# CHEM_CONTROL_BOX.net
KiCad netlist of a schematic drawn in Altium Designer
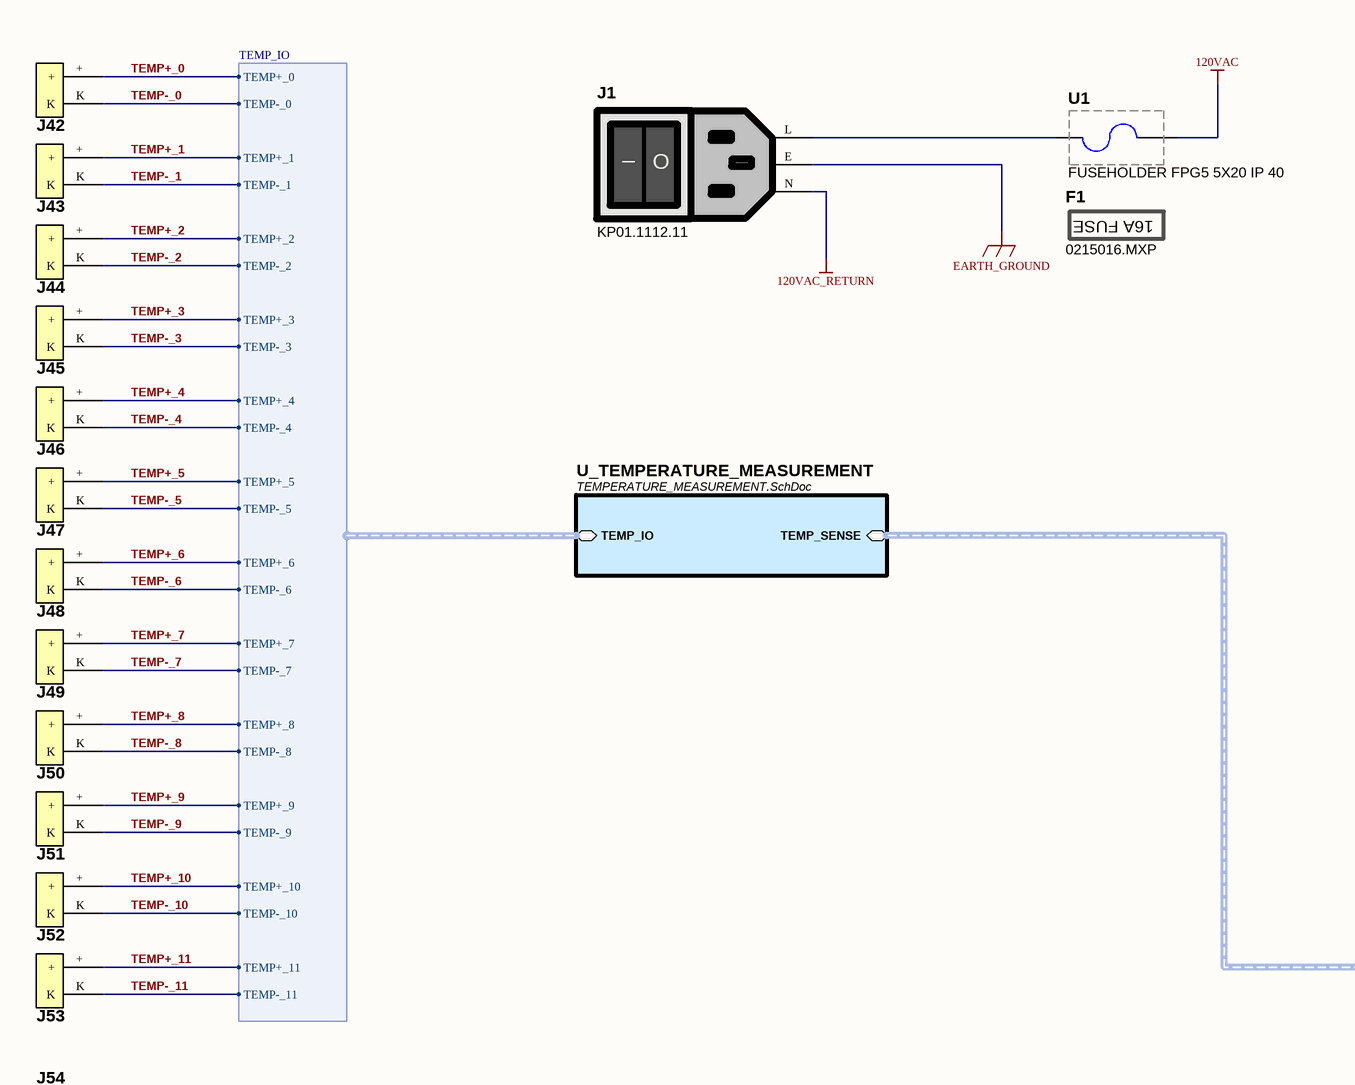
[diagram p0: CHEM_CONTROL_BOX.SchDoc, top left]
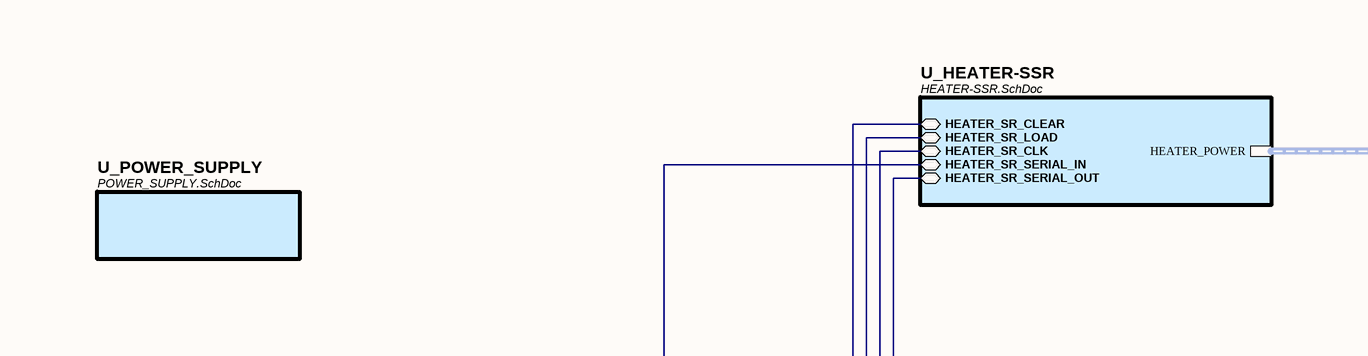
[diagram p1: CHEM_CONTROL_BOX.SchDoc, top middle]
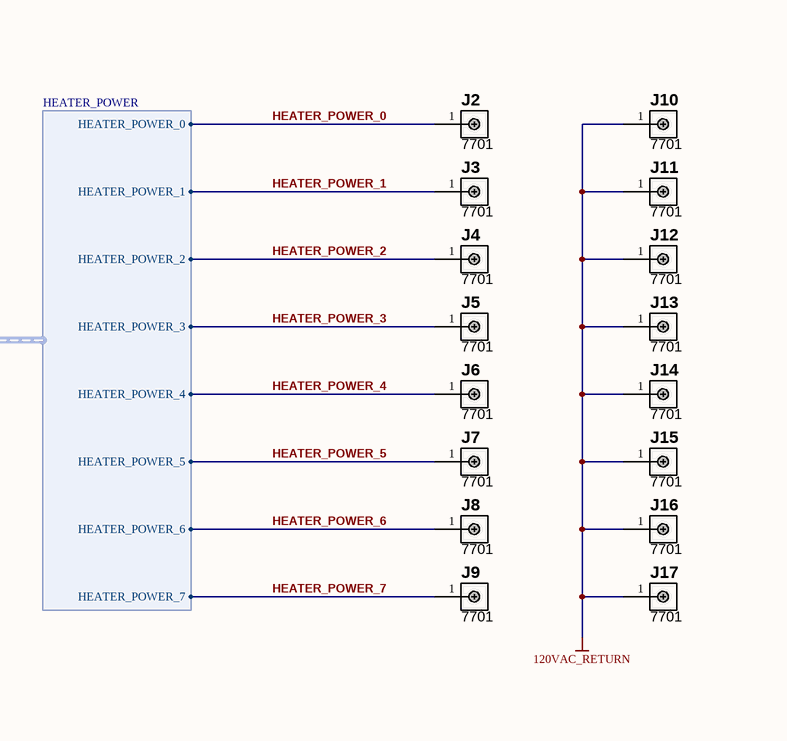
[diagram p2: CHEM_CONTROL_BOX.SchDoc, top right]
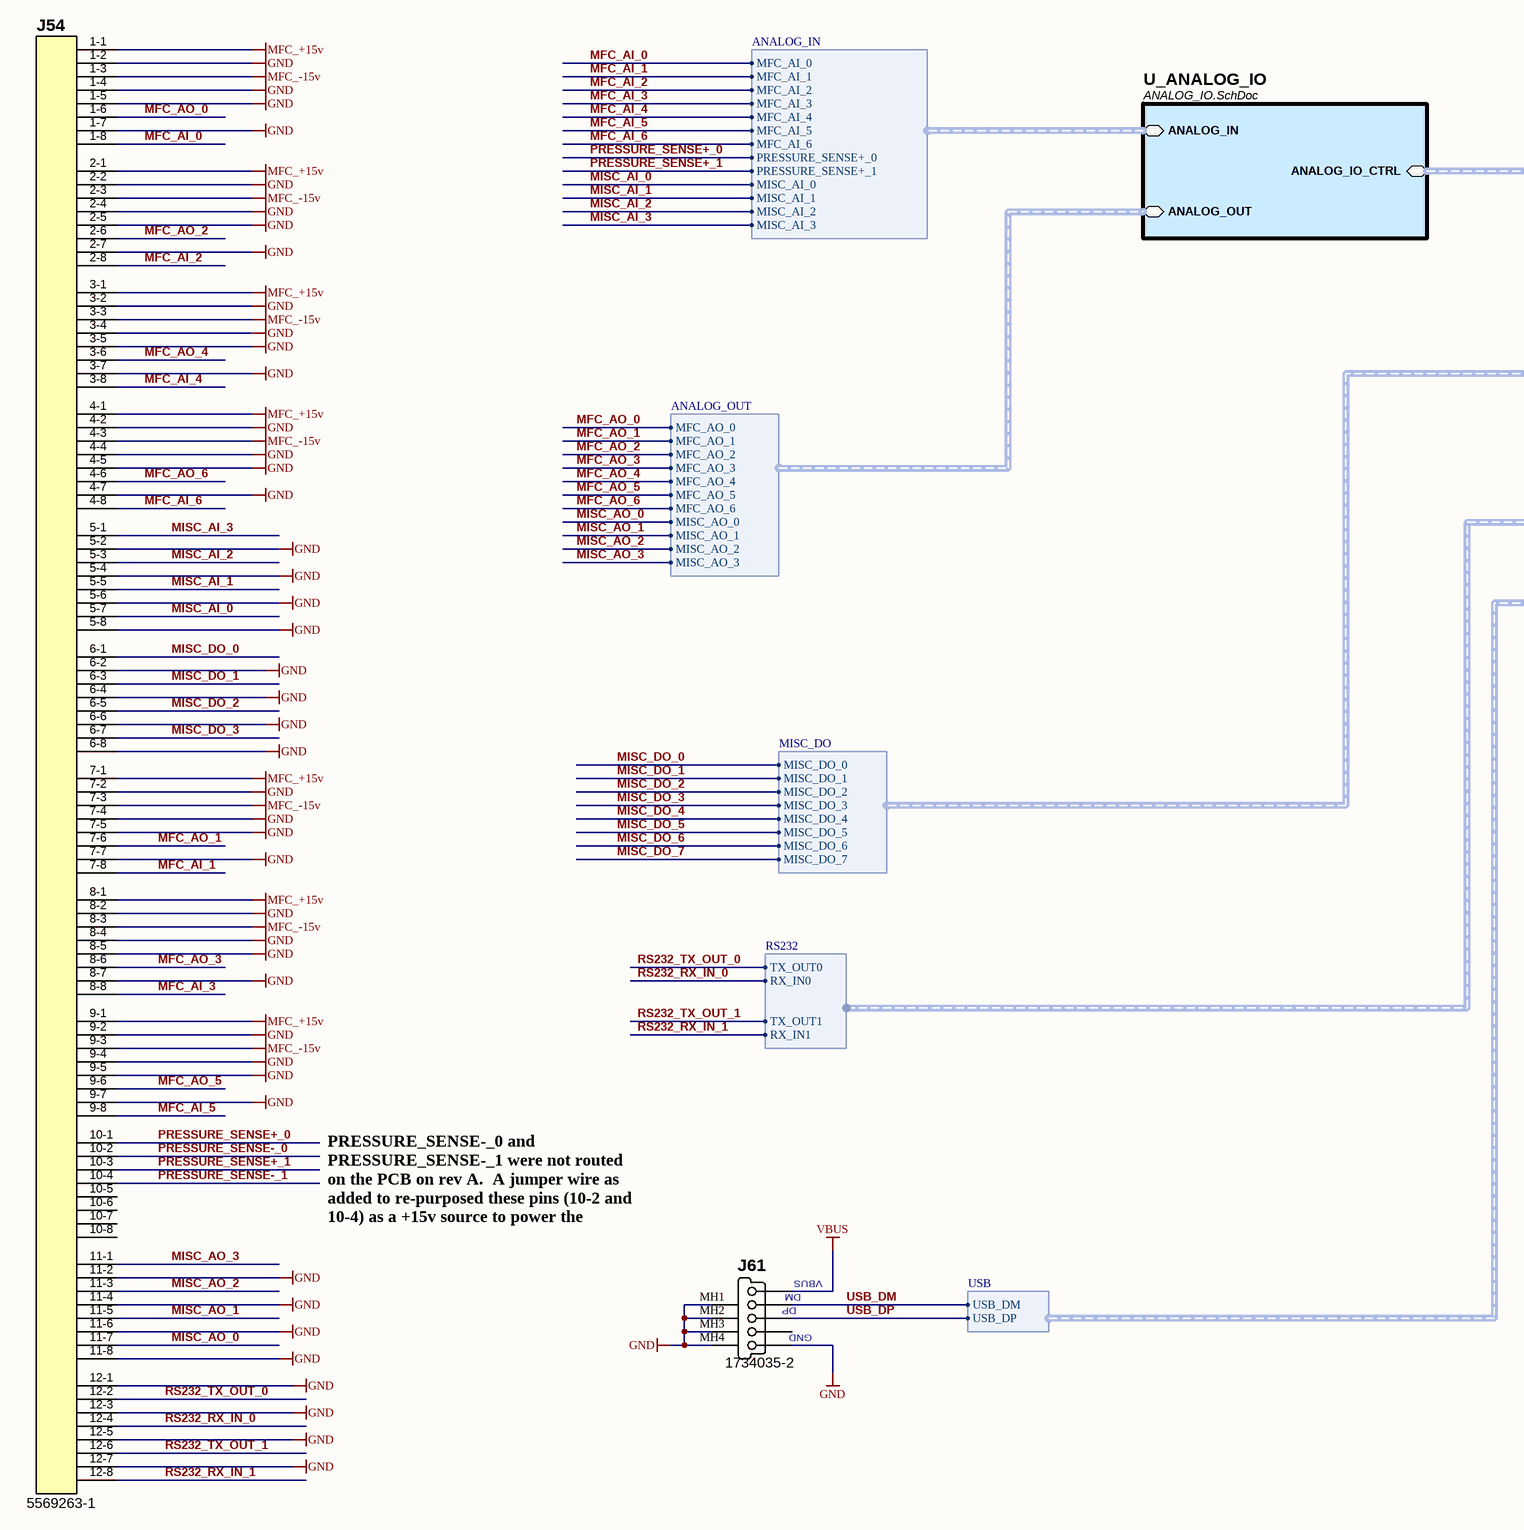
[diagram p3: CHEM_CONTROL_BOX.SchDoc, bottom left]
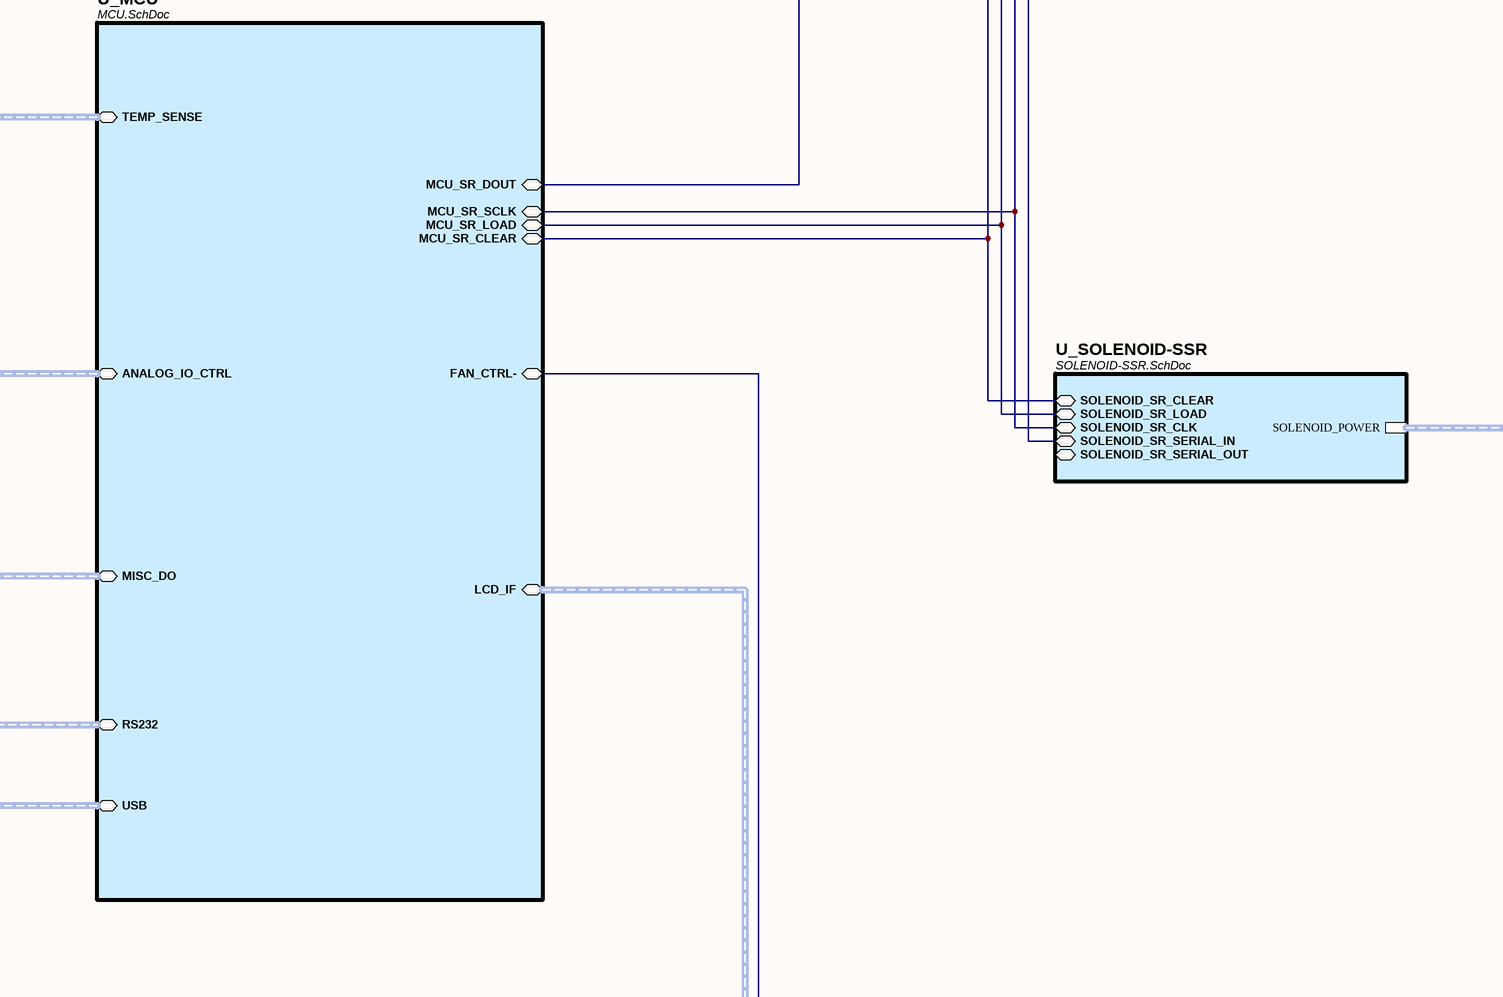
[diagram p4: CHEM_CONTROL_BOX.SchDoc, bottom middle]
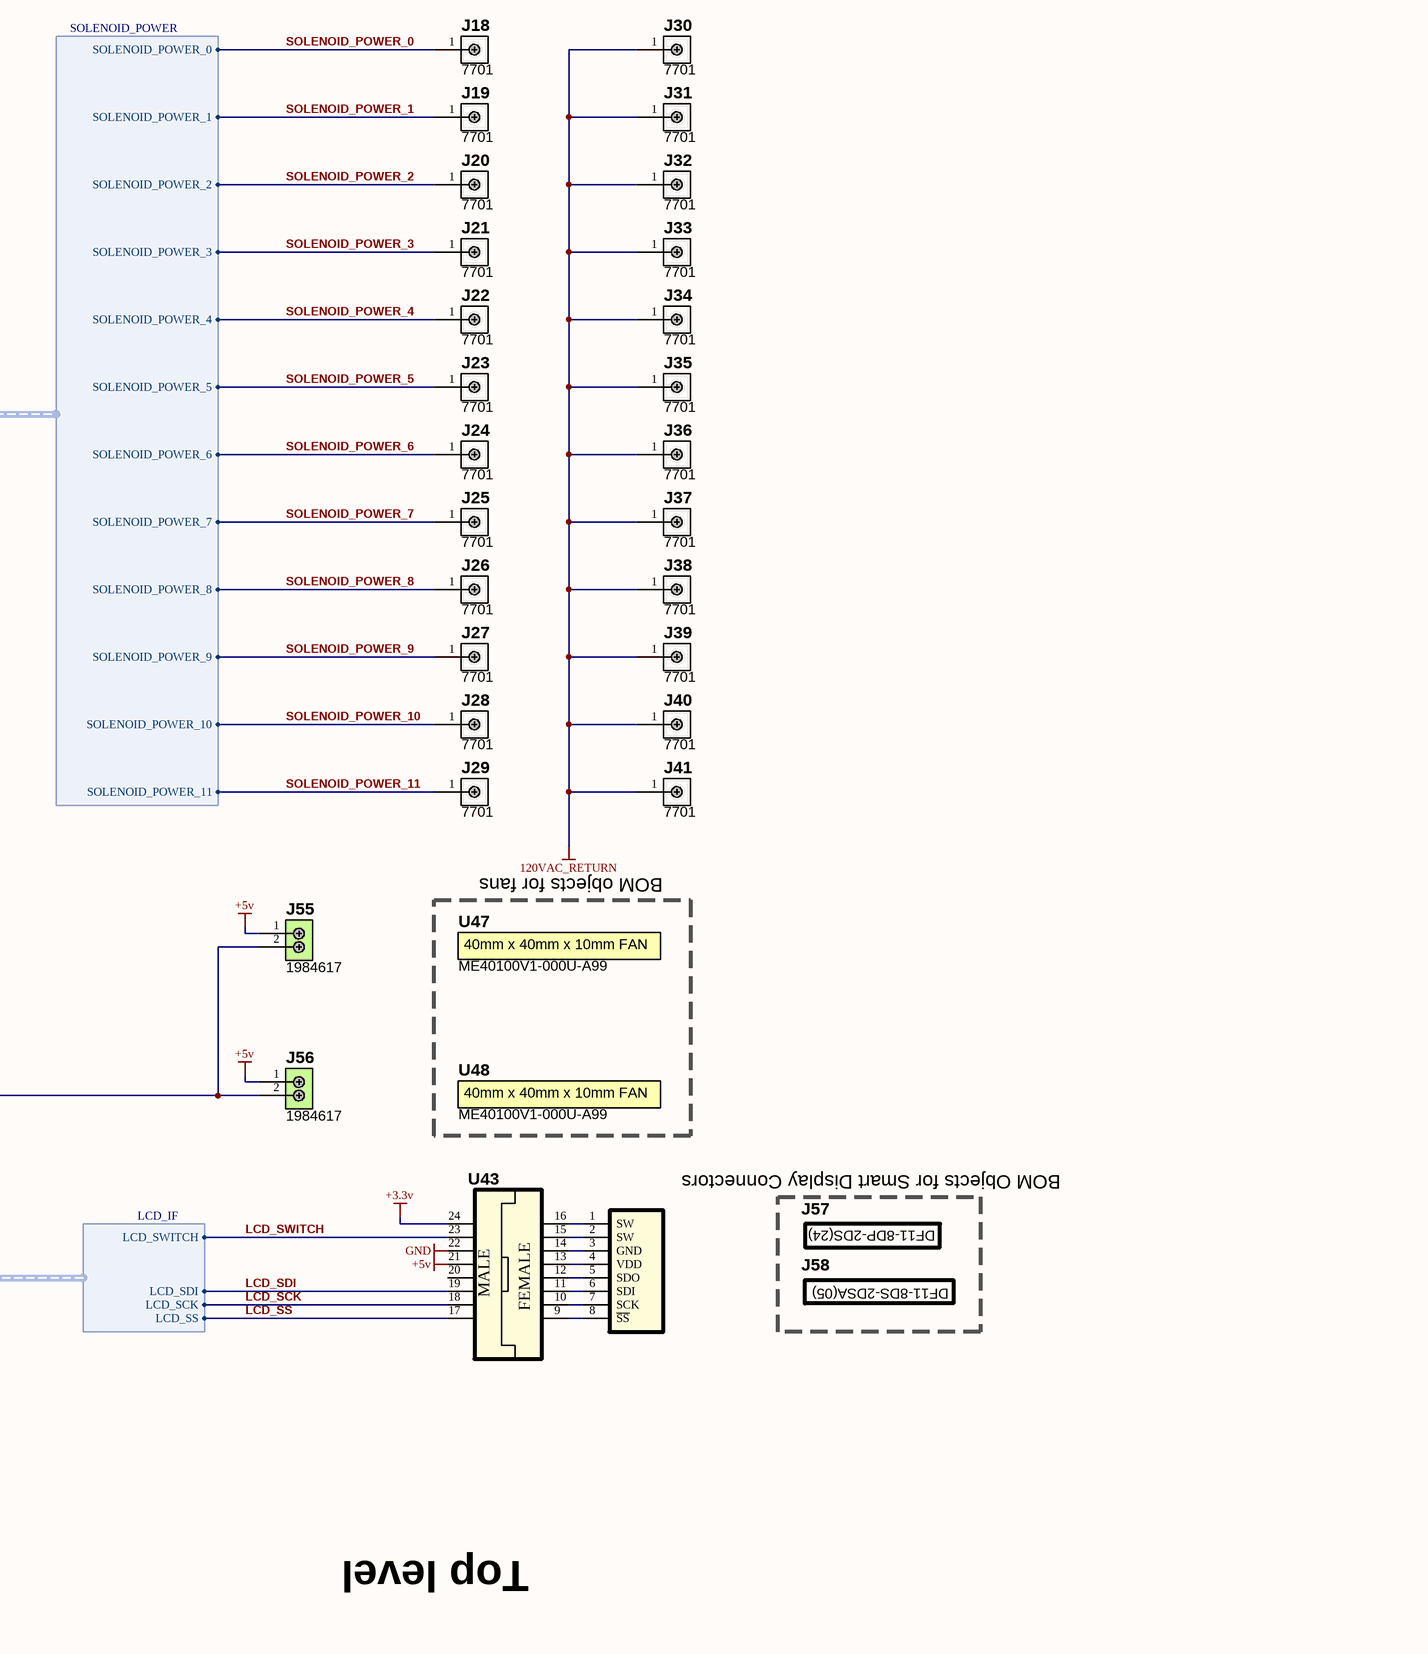
[diagram p5: CHEM_CONTROL_BOX.SchDoc, bottom right]

(export (version "E")
  (design (tool "Eeschema 10.0.6"))
  (components
    (comp (ref "F1")
      (value "0215016.MXP")
      (description "FUSE 16A 250VAC 5X20 SLOW")
      (fields (field (name "MANUFACTURER") "Littelfuse Inc"))
      (libsource (lib "eBOM_Items") (part "0215016.MXP"))
    )
    (comp (ref "J1")
      (value "KP01.1112.11")
      (footprint "KP01.1112.11")
      (description "AC Power Entry Modules SNAP-N PCB 2-POLE")
      (fields (field (name "MANUFACTURER") "Schurter"))
      (libsource (lib "eModule") (part "KP01.1112.11"))
    )
    (comp (ref "J2")
      (value "7701")
      (footprint "7701")
      (description "TERM W/ASSEMBLD SCREW VERT PCMNT")
      (fields (field (name "MANUFACTURER") "Keystone Electronics"))
      (libsource (lib "eConnector") (part "7701"))
    )
    (comp (ref "J3")
      (value "7701")
      (footprint "7701")
      (description "TERM W/ASSEMBLD SCREW VERT PCMNT")
      (fields (field (name "MANUFACTURER") "Keystone Electronics"))
      (libsource (lib "eConnector") (part "7701"))
    )
    (comp (ref "J4")
      (value "7701")
      (footprint "7701")
      (description "TERM W/ASSEMBLD SCREW VERT PCMNT")
      (fields (field (name "MANUFACTURER") "Keystone Electronics"))
      (libsource (lib "eConnector") (part "7701"))
    )
    (comp (ref "J5")
      (value "7701")
      (footprint "7701")
      (description "TERM W/ASSEMBLD SCREW VERT PCMNT")
      (fields (field (name "MANUFACTURER") "Keystone Electronics"))
      (libsource (lib "eConnector") (part "7701"))
    )
    (comp (ref "J6")
      (value "7701")
      (footprint "7701")
      (description "TERM W/ASSEMBLD SCREW VERT PCMNT")
      (fields (field (name "MANUFACTURER") "Keystone Electronics"))
      (libsource (lib "eConnector") (part "7701"))
    )
    (comp (ref "J7")
      (value "7701")
      (footprint "7701")
      (description "TERM W/ASSEMBLD SCREW VERT PCMNT")
      (fields (field (name "MANUFACTURER") "Keystone Electronics"))
      (libsource (lib "eConnector") (part "7701"))
    )
    (comp (ref "J8")
      (value "7701")
      (footprint "7701")
      (description "TERM W/ASSEMBLD SCREW VERT PCMNT")
      (fields (field (name "MANUFACTURER") "Keystone Electronics"))
      (libsource (lib "eConnector") (part "7701"))
    )
    (comp (ref "J9")
      (value "7701")
      (footprint "7701")
      (description "TERM W/ASSEMBLD SCREW VERT PCMNT")
      (fields (field (name "MANUFACTURER") "Keystone Electronics"))
      (libsource (lib "eConnector") (part "7701"))
    )
    (comp (ref "J10")
      (value "7701")
      (footprint "7701")
      (description "TERM W/ASSEMBLD SCREW VERT PCMNT")
      (fields (field (name "MANUFACTURER") "Keystone Electronics"))
      (libsource (lib "eConnector") (part "7701"))
    )
    (comp (ref "J11")
      (value "7701")
      (footprint "7701")
      (description "TERM W/ASSEMBLD SCREW VERT PCMNT")
      (fields (field (name "MANUFACTURER") "Keystone Electronics"))
      (libsource (lib "eConnector") (part "7701"))
    )
    (comp (ref "J12")
      (value "7701")
      (footprint "7701")
      (description "TERM W/ASSEMBLD SCREW VERT PCMNT")
      (fields (field (name "MANUFACTURER") "Keystone Electronics"))
      (libsource (lib "eConnector") (part "7701"))
    )
    (comp (ref "J13")
      (value "7701")
      (footprint "7701")
      (description "TERM W/ASSEMBLD SCREW VERT PCMNT")
      (fields (field (name "MANUFACTURER") "Keystone Electronics"))
      (libsource (lib "eConnector") (part "7701"))
    )
    (comp (ref "J14")
      (value "7701")
      (footprint "7701")
      (description "TERM W/ASSEMBLD SCREW VERT PCMNT")
      (fields (field (name "MANUFACTURER") "Keystone Electronics"))
      (libsource (lib "eConnector") (part "7701"))
    )
    (comp (ref "J15")
      (value "7701")
      (footprint "7701")
      (description "TERM W/ASSEMBLD SCREW VERT PCMNT")
      (fields (field (name "MANUFACTURER") "Keystone Electronics"))
      (libsource (lib "eConnector") (part "7701"))
    )
    (comp (ref "J16")
      (value "7701")
      (footprint "7701")
      (description "TERM W/ASSEMBLD SCREW VERT PCMNT")
      (fields (field (name "MANUFACTURER") "Keystone Electronics"))
      (libsource (lib "eConnector") (part "7701"))
    )
    (comp (ref "J17")
      (value "7701")
      (footprint "7701")
      (description "TERM W/ASSEMBLD SCREW VERT PCMNT")
      (fields (field (name "MANUFACTURER") "Keystone Electronics"))
      (libsource (lib "eConnector") (part "7701"))
    )
    (comp (ref "J18")
      (value "7701")
      (footprint "7701")
      (description "TERM W/ASSEMBLD SCREW VERT PCMNT")
      (fields (field (name "MANUFACTURER") "Keystone Electronics"))
      (libsource (lib "eConnector") (part "7701"))
    )
    (comp (ref "J19")
      (value "7701")
      (footprint "7701")
      (description "TERM W/ASSEMBLD SCREW VERT PCMNT")
      (fields (field (name "MANUFACTURER") "Keystone Electronics"))
      (libsource (lib "eConnector") (part "7701"))
    )
    (comp (ref "J20")
      (value "7701")
      (footprint "7701")
      (description "TERM W/ASSEMBLD SCREW VERT PCMNT")
      (fields (field (name "MANUFACTURER") "Keystone Electronics"))
      (libsource (lib "eConnector") (part "7701"))
    )
    (comp (ref "J21")
      (value "7701")
      (footprint "7701")
      (description "TERM W/ASSEMBLD SCREW VERT PCMNT")
      (fields (field (name "MANUFACTURER") "Keystone Electronics"))
      (libsource (lib "eConnector") (part "7701"))
    )
    (comp (ref "J22")
      (value "7701")
      (footprint "7701")
      (description "TERM W/ASSEMBLD SCREW VERT PCMNT")
      (fields (field (name "MANUFACTURER") "Keystone Electronics"))
      (libsource (lib "eConnector") (part "7701"))
    )
    (comp (ref "J23")
      (value "7701")
      (footprint "7701")
      (description "TERM W/ASSEMBLD SCREW VERT PCMNT")
      (fields (field (name "MANUFACTURER") "Keystone Electronics"))
      (libsource (lib "eConnector") (part "7701"))
    )
    (comp (ref "J24")
      (value "7701")
      (footprint "7701")
      (description "TERM W/ASSEMBLD SCREW VERT PCMNT")
      (fields (field (name "MANUFACTURER") "Keystone Electronics"))
      (libsource (lib "eConnector") (part "7701"))
    )
    (comp (ref "J25")
      (value "7701")
      (footprint "7701")
      (description "TERM W/ASSEMBLD SCREW VERT PCMNT")
      (fields (field (name "MANUFACTURER") "Keystone Electronics"))
      (libsource (lib "eConnector") (part "7701"))
    )
    (comp (ref "J26")
      (value "7701")
      (footprint "7701")
      (description "TERM W/ASSEMBLD SCREW VERT PCMNT")
      (fields (field (name "MANUFACTURER") "Keystone Electronics"))
      (libsource (lib "eConnector") (part "7701"))
    )
    (comp (ref "J27")
      (value "7701")
      (footprint "7701")
      (description "TERM W/ASSEMBLD SCREW VERT PCMNT")
      (fields (field (name "MANUFACTURER") "Keystone Electronics"))
      (libsource (lib "eConnector") (part "7701"))
    )
    (comp (ref "J28")
      (value "7701")
      (footprint "7701")
      (description "TERM W/ASSEMBLD SCREW VERT PCMNT")
      (fields (field (name "MANUFACTURER") "Keystone Electronics"))
      (libsource (lib "eConnector") (part "7701"))
    )
    (comp (ref "J29")
      (value "7701")
      (footprint "7701")
      (description "TERM W/ASSEMBLD SCREW VERT PCMNT")
      (fields (field (name "MANUFACTURER") "Keystone Electronics"))
      (libsource (lib "eConnector") (part "7701"))
    )
    (comp (ref "J30")
      (value "7701")
      (footprint "7701")
      (description "TERM W/ASSEMBLD SCREW VERT PCMNT")
      (fields (field (name "MANUFACTURER") "Keystone Electronics"))
      (libsource (lib "eConnector") (part "7701"))
    )
    (comp (ref "J31")
      (value "7701")
      (footprint "7701")
      (description "TERM W/ASSEMBLD SCREW VERT PCMNT")
      (fields (field (name "MANUFACTURER") "Keystone Electronics"))
      (libsource (lib "eConnector") (part "7701"))
    )
    (comp (ref "J32")
      (value "7701")
      (footprint "7701")
      (description "TERM W/ASSEMBLD SCREW VERT PCMNT")
      (fields (field (name "MANUFACTURER") "Keystone Electronics"))
      (libsource (lib "eConnector") (part "7701"))
    )
    (comp (ref "J33")
      (value "7701")
      (footprint "7701")
      (description "TERM W/ASSEMBLD SCREW VERT PCMNT")
      (fields (field (name "MANUFACTURER") "Keystone Electronics"))
      (libsource (lib "eConnector") (part "7701"))
    )
    (comp (ref "J34")
      (value "7701")
      (footprint "7701")
      (description "TERM W/ASSEMBLD SCREW VERT PCMNT")
      (fields (field (name "MANUFACTURER") "Keystone Electronics"))
      (libsource (lib "eConnector") (part "7701"))
    )
    (comp (ref "J35")
      (value "7701")
      (footprint "7701")
      (description "TERM W/ASSEMBLD SCREW VERT PCMNT")
      (fields (field (name "MANUFACTURER") "Keystone Electronics"))
      (libsource (lib "eConnector") (part "7701"))
    )
    (comp (ref "J36")
      (value "7701")
      (footprint "7701")
      (description "TERM W/ASSEMBLD SCREW VERT PCMNT")
      (fields (field (name "MANUFACTURER") "Keystone Electronics"))
      (libsource (lib "eConnector") (part "7701"))
    )
    (comp (ref "J37")
      (value "7701")
      (footprint "7701")
      (description "TERM W/ASSEMBLD SCREW VERT PCMNT")
      (fields (field (name "MANUFACTURER") "Keystone Electronics"))
      (libsource (lib "eConnector") (part "7701"))
    )
    (comp (ref "J38")
      (value "7701")
      (footprint "7701")
      (description "TERM W/ASSEMBLD SCREW VERT PCMNT")
      (fields (field (name "MANUFACTURER") "Keystone Electronics"))
      (libsource (lib "eConnector") (part "7701"))
    )
    (comp (ref "J39")
      (value "7701")
      (footprint "7701")
      (description "TERM W/ASSEMBLD SCREW VERT PCMNT")
      (fields (field (name "MANUFACTURER") "Keystone Electronics"))
      (libsource (lib "eConnector") (part "7701"))
    )
    (comp (ref "J40")
      (value "7701")
      (footprint "7701")
      (description "TERM W/ASSEMBLD SCREW VERT PCMNT")
      (fields (field (name "MANUFACTURER") "Keystone Electronics"))
      (libsource (lib "eConnector") (part "7701"))
    )
    (comp (ref "J41")
      (value "7701")
      (footprint "7701")
      (description "TERM W/ASSEMBLD SCREW VERT PCMNT")
      (fields (field (name "MANUFACTURER") "Keystone Electronics"))
      (libsource (lib "eConnector") (part "7701"))
    )
    (comp (ref "J42")
      (value "PCC-SMP-K")
      (footprint "PCC-SMP-V")
      (description "Vertical K type thermocouple connector - K")
      (fields (field (name "MANUFACTURER") "Omega"))
      (libsource (lib "eConnector") (part "PCC-SMP-K-100"))
    )
    (comp (ref "J43")
      (value "PCC-SMP-K")
      (footprint "PCC-SMP-V")
      (description "Vertical K type thermocouple connector - K")
      (fields (field (name "MANUFACTURER") "Omega"))
      (libsource (lib "eConnector") (part "PCC-SMP-K-100"))
    )
    (comp (ref "J44")
      (value "PCC-SMP-K")
      (footprint "PCC-SMP-V")
      (description "Vertical K type thermocouple connector - K")
      (fields (field (name "MANUFACTURER") "Omega"))
      (libsource (lib "eConnector") (part "PCC-SMP-K-100"))
    )
    (comp (ref "J45")
      (value "PCC-SMP-K")
      (footprint "PCC-SMP-V")
      (description "Vertical K type thermocouple connector - K")
      (fields (field (name "MANUFACTURER") "Omega"))
      (libsource (lib "eConnector") (part "PCC-SMP-K-100"))
    )
    (comp (ref "J46")
      (value "PCC-SMP-K")
      (footprint "PCC-SMP-V")
      (description "Vertical K type thermocouple connector - K")
      (fields (field (name "MANUFACTURER") "Omega"))
      (libsource (lib "eConnector") (part "PCC-SMP-K-100"))
    )
    (comp (ref "J47")
      (value "PCC-SMP-K")
      (footprint "PCC-SMP-V")
      (description "Vertical K type thermocouple connector - K")
      (fields (field (name "MANUFACTURER") "Omega"))
      (libsource (lib "eConnector") (part "PCC-SMP-K-100"))
    )
    (comp (ref "J48")
      (value "PCC-SMP-K")
      (footprint "PCC-SMP-V")
      (description "Vertical K type thermocouple connector - K")
      (fields (field (name "MANUFACTURER") "Omega"))
      (libsource (lib "eConnector") (part "PCC-SMP-K-100"))
    )
    (comp (ref "J49")
      (value "PCC-SMP-K")
      (footprint "PCC-SMP-V")
      (description "Vertical K type thermocouple connector - K")
      (fields (field (name "MANUFACTURER") "Omega"))
      (libsource (lib "eConnector") (part "PCC-SMP-K-100"))
    )
    (comp (ref "J50")
      (value "PCC-SMP-K")
      (footprint "PCC-SMP-V")
      (description "Vertical K type thermocouple connector - K")
      (fields (field (name "MANUFACTURER") "Omega"))
      (libsource (lib "eConnector") (part "PCC-SMP-K-100"))
    )
    (comp (ref "J51")
      (value "PCC-SMP-K")
      (footprint "PCC-SMP-V")
      (description "Vertical K type thermocouple connector - K")
      (fields (field (name "MANUFACTURER") "Omega"))
      (libsource (lib "eConnector") (part "PCC-SMP-K-100"))
    )
    (comp (ref "J52")
      (value "PCC-SMP-K")
      (footprint "PCC-SMP-V")
      (description "Vertical K type thermocouple connector - K")
      (fields (field (name "MANUFACTURER") "Omega"))
      (libsource (lib "eConnector") (part "PCC-SMP-K-100"))
    )
    (comp (ref "J53")
      (value "PCC-SMP-K")
      (footprint "PCC-SMP-V")
      (description "Vertical K type thermocouple connector - K")
      (fields (field (name "MANUFACTURER") "Omega"))
      (libsource (lib "eConnector") (part "PCC-SMP-K-100"))
    )
    (comp (ref "J54")
      (value "5569263-1")
      (footprint "5569263-1")
      (description "CONN MOD JACK R/A 8P8C SHIELDED")
      (fields (field (name "MANUFACTURER") "TE Connectivity"))
      (libsource (lib "eConnector") (part "5569263-1"))
    )
    (comp (ref "J55")
      (value "1984617")
      (footprint "1984617")
      (description "CONN TERM BLOCK T/H 2POS 3.5MM")
      (fields (field (name "MANUFACTURER") "Phoenix Contact") (field (name "VOLTAGE") "300V"))
      (libsource (lib "eConnector") (part "1984617"))
    )
    (comp (ref "J56")
      (value "1984617")
      (footprint "1984617")
      (description "CONN TERM BLOCK T/H 2POS 3.5MM")
      (fields (field (name "MANUFACTURER") "Phoenix Contact") (field (name "VOLTAGE") "300V"))
      (libsource (lib "eConnector") (part "1984617"))
    )
    (comp (ref "J57")
      (value "DF11-8DP-2DS(24)")
      (description "CONN HEADER 8POS 2MM RT ANG TIN")
      (fields (field (name "MANUFACTURER") "Hirose Electric Co Ltd"))
      (libsource (lib "151214_2") (part "DF11-8DP-2DS(24) (BOM ITEM)"))
    )
    (comp (ref "J58")
      (value "DF11-8DS-2DSA(05)")
      (description "CONN RECEPT 8POS 2MM PCB TIN")
      (fields (field (name "MANUFACTURER") "Hirose Electric Co Ltd"))
      (libsource (lib "151214_2") (part "DF11-8DS-2DSA(05) (BOM ITEM)"))
    )
    (comp (ref "J61")
      (value "1734035-2")
      (footprint "1734035-2")
      (fields (field (name "MANUFACTURER") "TE Connectivity"))
      (libsource (lib "eConnector") (part "1734035-2"))
    )
    (comp (ref "U1")
      (value "FUSEHOLDER FPG5 5X20 IP 40")
      (footprint "3101.0055")
      (fields
        (field (name "MANUFACTURER") "Schurter Inc")
        (field (name "MANUFACTURER PART NUMBER") "3101.0055")
        (field (name "VOLTAGE") "250V")
      )
      (libsource (lib "eElectroMechanical") (part "3101.0055"))
    )
    (comp (ref "U43")
      (value "IS15DSBFP4RGB")
      (footprint "R/A IS15DSBFP4RGB")
      (description "64x32 Compact Smart Switch")
      (fields (field (name "MANUFACTURER") "NKK Switches"))
      (libsource (lib "eModule") (part "R/A IS15DSBFP4RGB"))
    )
    (comp (ref "U47")
      (value "ME40100V1-000U-A99")
      (footprint "ME40100V1-000U-A99")
      (description "FAN 40X10MM 5VDC 1.08W 8CFM")
      (fields (field (name "MANUFACTURER") "Sunon Fans"))
      (libsource (lib "eElectroMechanical") (part "ME40100V1-000U-A99"))
    )
    (comp (ref "U48")
      (value "ME40100V1-000U-A99")
      (footprint "ME40100V1-000U-A99")
      (description "FAN 40X10MM 5VDC 1.08W 8CFM")
      (fields (field (name "MANUFACTURER") "Sunon Fans"))
      (libsource (lib "eElectroMechanical") (part "ME40100V1-000U-A99"))
    )
  )
  (nets
    (net (code "10") (name "+3.3v") (class "Default")
      (node (ref "U43") (pin "24") (pinfunction "24_24") (pintype "passive"))
    )
    (net (code "11") (name "+5v") (class "Default")
      (node (ref "J55") (pin "1") (pinfunction "1_1") (pintype "passive"))
      (node (ref "J56") (pin "1") (pinfunction "1_1") (pintype "passive"))
      (node (ref "U43") (pin "21") (pinfunction "21_21") (pintype "passive"))
    )
    (net (code "13") (name "/FAN_CTRL-") (class "Default")
      (node (ref "J55") (pin "2") (pinfunction "2_2") (pintype "passive"))
      (node (ref "J56") (pin "2") (pinfunction "2_2") (pintype "passive"))
    )
    (net (code "14") (name "/HEATER_POWER_0") (class "Default")
      (node (ref "J2") (pin "1") (pinfunction "1_1") (pintype "passive"))
    )
    (net (code "15") (name "/HEATER_POWER_1") (class "Default")
      (node (ref "J3") (pin "1") (pinfunction "1_1") (pintype "passive"))
    )
    (net (code "16") (name "/HEATER_POWER_2") (class "Default")
      (node (ref "J4") (pin "1") (pinfunction "1_1") (pintype "passive"))
    )
    (net (code "17") (name "/HEATER_POWER_3") (class "Default")
      (node (ref "J5") (pin "1") (pinfunction "1_1") (pintype "passive"))
    )
    (net (code "18") (name "/HEATER_POWER_4") (class "Default")
      (node (ref "J6") (pin "1") (pinfunction "1_1") (pintype "passive"))
    )
    (net (code "19") (name "/HEATER_POWER_5") (class "Default")
      (node (ref "J7") (pin "1") (pinfunction "1_1") (pintype "passive"))
    )
    (net (code "20") (name "/HEATER_POWER_6") (class "Default")
      (node (ref "J8") (pin "1") (pinfunction "1_1") (pintype "passive"))
    )
    (net (code "21") (name "/HEATER_POWER_7") (class "Default")
      (node (ref "J9") (pin "1") (pinfunction "1_1") (pintype "passive"))
    )
    (net (code "27") (name "/LCD_SCK") (class "Default")
      (node (ref "U43") (pin "18") (pinfunction "18_18") (pintype "passive"))
    )
    (net (code "28") (name "/LCD_SDI") (class "Default")
      (node (ref "U43") (pin "19") (pinfunction "19_19") (pintype "passive"))
    )
    (net (code "29") (name "/LCD_SS") (class "Default")
      (node (ref "U43") (pin "17") (pinfunction "17_17") (pintype "passive"))
    )
    (net (code "30") (name "/LCD_SWITCH") (class "Default")
      (node (ref "U43") (pin "23") (pinfunction "23_23") (pintype "passive"))
    )
    (net (code "31") (name "/MFC_AI_0") (class "Default")
      (node (ref "J54") (pin "1-8") (pinfunction "1-8_1-8") (pintype "passive"))
    )
    (net (code "32") (name "/MFC_AI_1") (class "Default")
      (node (ref "J54") (pin "7-8") (pinfunction "7-8_7-8") (pintype "passive"))
    )
    (net (code "33") (name "/MFC_AI_2") (class "Default")
      (node (ref "J54") (pin "2-8") (pinfunction "2-8_2-8") (pintype "passive"))
    )
    (net (code "34") (name "/MFC_AI_3") (class "Default")
      (node (ref "J54") (pin "8-8") (pinfunction "8-8_8-8") (pintype "passive"))
    )
    (net (code "35") (name "/MFC_AI_4") (class "Default")
      (node (ref "J54") (pin "3-8") (pinfunction "3-8_3-8") (pintype "passive"))
    )
    (net (code "36") (name "/MFC_AI_5") (class "Default")
      (node (ref "J54") (pin "9-8") (pinfunction "9-8_9-8") (pintype "passive"))
    )
    (net (code "37") (name "/MFC_AI_6") (class "Default")
      (node (ref "J54") (pin "4-8") (pinfunction "4-8_4-8") (pintype "passive"))
    )
    (net (code "38") (name "/MFC_AO_0") (class "Default")
      (node (ref "J54") (pin "1-6") (pinfunction "1-6_1-6") (pintype "passive"))
    )
    (net (code "39") (name "/MFC_AO_1") (class "Default")
      (node (ref "J54") (pin "7-6") (pinfunction "7-6_7-6") (pintype "passive"))
    )
    (net (code "40") (name "/MFC_AO_2") (class "Default")
      (node (ref "J54") (pin "2-6") (pinfunction "2-6_2-6") (pintype "passive"))
    )
    (net (code "41") (name "/MFC_AO_3") (class "Default")
      (node (ref "J54") (pin "8-6") (pinfunction "8-6_8-6") (pintype "passive"))
    )
    (net (code "42") (name "/MFC_AO_4") (class "Default")
      (node (ref "J54") (pin "3-6") (pinfunction "3-6_3-6") (pintype "passive"))
    )
    (net (code "43") (name "/MFC_AO_5") (class "Default")
      (node (ref "J54") (pin "9-6") (pinfunction "9-6_9-6") (pintype "passive"))
    )
    (net (code "44") (name "/MFC_AO_6") (class "Default")
      (node (ref "J54") (pin "4-6") (pinfunction "4-6_4-6") (pintype "passive"))
    )
    (net (code "45") (name "/MISC_AI_0") (class "Default")
      (node (ref "J54") (pin "5-7") (pinfunction "5-7_5-7") (pintype "passive"))
    )
    (net (code "46") (name "/MISC_AI_1") (class "Default")
      (node (ref "J54") (pin "5-5") (pinfunction "5-5_5-5") (pintype "passive"))
    )
    (net (code "47") (name "/MISC_AI_2") (class "Default")
      (node (ref "J54") (pin "5-3") (pinfunction "5-3_5-3") (pintype "passive"))
    )
    (net (code "48") (name "/MISC_AI_3") (class "Default")
      (node (ref "J54") (pin "5-1") (pinfunction "5-1_5-1") (pintype "passive"))
    )
    (net (code "49") (name "/MISC_AO_0") (class "Default")
      (node (ref "J54") (pin "11-7") (pinfunction "11-7_11-7") (pintype "passive"))
    )
    (net (code "50") (name "/MISC_AO_1") (class "Default")
      (node (ref "J54") (pin "11-5") (pinfunction "11-5_11-5") (pintype "passive"))
    )
    (net (code "51") (name "/MISC_AO_2") (class "Default")
      (node (ref "J54") (pin "11-3") (pinfunction "11-3_11-3") (pintype "passive"))
    )
    (net (code "52") (name "/MISC_AO_3") (class "Default")
      (node (ref "J54") (pin "11-1") (pinfunction "11-1_11-1") (pintype "passive"))
    )
    (net (code "53") (name "/MISC_DO_0") (class "Default")
      (node (ref "J54") (pin "6-1") (pinfunction "6-1_6-1") (pintype "passive"))
    )
    (net (code "54") (name "/MISC_DO_1") (class "Default")
      (node (ref "J54") (pin "6-3") (pinfunction "6-3_6-3") (pintype "passive"))
    )
    (net (code "55") (name "/MISC_DO_2") (class "Default")
      (node (ref "J54") (pin "6-5") (pinfunction "6-5_6-5") (pintype "passive"))
    )
    (net (code "56") (name "/MISC_DO_3") (class "Default")
      (node (ref "J54") (pin "6-7") (pinfunction "6-7_6-7") (pintype "passive"))
    )
    (net (code "61") (name "/PRESSURE_SENSE+_0") (class "Default")
      (node (ref "J54") (pin "10-1") (pinfunction "10-1_10-1") (pintype "passive"))
    )
    (net (code "62") (name "/PRESSURE_SENSE+_1") (class "Default")
      (node (ref "J54") (pin "10-3") (pinfunction "10-3_10-3") (pintype "passive"))
    )
    (net (code "63") (name "/PRESSURE_SENSE-_0") (class "Default")
      (node (ref "J54") (pin "10-2") (pinfunction "10-2_10-2") (pintype "passive"))
    )
    (net (code "64") (name "/PRESSURE_SENSE-_1") (class "Default")
      (node (ref "J54") (pin "10-4") (pinfunction "10-4_10-4") (pintype "passive"))
    )
    (net (code "65") (name "/RS232_RX_IN_0") (class "Default")
      (node (ref "J54") (pin "12-4") (pinfunction "12-4_12-4") (pintype "passive"))
    )
    (net (code "66") (name "/RS232_RX_IN_1") (class "Default")
      (node (ref "J54") (pin "12-8") (pinfunction "12-8_12-8") (pintype "passive"))
    )
    (net (code "67") (name "/RS232_TX_OUT_0") (class "Default")
      (node (ref "J54") (pin "12-2") (pinfunction "12-2_12-2") (pintype "passive"))
    )
    (net (code "68") (name "/RS232_TX_OUT_1") (class "Default")
      (node (ref "J54") (pin "12-6") (pinfunction "12-6_12-6") (pintype "passive"))
    )
    (net (code "69") (name "/SOLENOID_POWER_0") (class "Default")
      (node (ref "J18") (pin "1") (pinfunction "1_1") (pintype "passive"))
    )
    (net (code "70") (name "/SOLENOID_POWER_1") (class "Default")
      (node (ref "J19") (pin "1") (pinfunction "1_1") (pintype "passive"))
    )
    (net (code "71") (name "/SOLENOID_POWER_2") (class "Default")
      (node (ref "J20") (pin "1") (pinfunction "1_1") (pintype "passive"))
    )
    (net (code "72") (name "/SOLENOID_POWER_3") (class "Default")
      (node (ref "J21") (pin "1") (pinfunction "1_1") (pintype "passive"))
    )
    (net (code "73") (name "/SOLENOID_POWER_4") (class "Default")
      (node (ref "J22") (pin "1") (pinfunction "1_1") (pintype "passive"))
    )
    (net (code "74") (name "/SOLENOID_POWER_5") (class "Default")
      (node (ref "J23") (pin "1") (pinfunction "1_1") (pintype "passive"))
    )
    (net (code "75") (name "/SOLENOID_POWER_6") (class "Default")
      (node (ref "J24") (pin "1") (pinfunction "1_1") (pintype "passive"))
    )
    (net (code "76") (name "/SOLENOID_POWER_7") (class "Default")
      (node (ref "J25") (pin "1") (pinfunction "1_1") (pintype "passive"))
    )
    (net (code "77") (name "/SOLENOID_POWER_8") (class "Default")
      (node (ref "J26") (pin "1") (pinfunction "1_1") (pintype "passive"))
    )
    (net (code "78") (name "/SOLENOID_POWER_9") (class "Default")
      (node (ref "J27") (pin "1") (pinfunction "1_1") (pintype "passive"))
    )
    (net (code "79") (name "/SOLENOID_POWER_10") (class "Default")
      (node (ref "J28") (pin "1") (pinfunction "1_1") (pintype "passive"))
    )
    (net (code "80") (name "/SOLENOID_POWER_11") (class "Default")
      (node (ref "J29") (pin "1") (pinfunction "1_1") (pintype "passive"))
    )
    (net (code "82") (name "/TEMP+_0") (class "Default")
      (node (ref "J42") (pin "+") (pinfunction "+_+") (pintype "passive"))
    )
    (net (code "83") (name "/TEMP+_1") (class "Default")
      (node (ref "J43") (pin "+") (pinfunction "+_+") (pintype "passive"))
    )
    (net (code "84") (name "/TEMP+_2") (class "Default")
      (node (ref "J44") (pin "+") (pinfunction "+_+") (pintype "passive"))
    )
    (net (code "85") (name "/TEMP+_3") (class "Default")
      (node (ref "J45") (pin "+") (pinfunction "+_+") (pintype "passive"))
    )
    (net (code "86") (name "/TEMP+_4") (class "Default")
      (node (ref "J46") (pin "+") (pinfunction "+_+") (pintype "passive"))
    )
    (net (code "87") (name "/TEMP+_5") (class "Default")
      (node (ref "J47") (pin "+") (pinfunction "+_+") (pintype "passive"))
    )
    (net (code "88") (name "/TEMP+_6") (class "Default")
      (node (ref "J48") (pin "+") (pinfunction "+_+") (pintype "passive"))
    )
    (net (code "89") (name "/TEMP+_7") (class "Default")
      (node (ref "J49") (pin "+") (pinfunction "+_+") (pintype "passive"))
    )
    (net (code "90") (name "/TEMP+_8") (class "Default")
      (node (ref "J50") (pin "+") (pinfunction "+_+") (pintype "passive"))
    )
    (net (code "91") (name "/TEMP+_9") (class "Default")
      (node (ref "J51") (pin "+") (pinfunction "+_+") (pintype "passive"))
    )
    (net (code "92") (name "/TEMP+_10") (class "Default")
      (node (ref "J52") (pin "+") (pinfunction "+_+") (pintype "passive"))
    )
    (net (code "93") (name "/TEMP+_11") (class "Default")
      (node (ref "J53") (pin "+") (pinfunction "+_+") (pintype "passive"))
    )
    (net (code "94") (name "/TEMP-_0") (class "Default")
      (node (ref "J42") (pin "K") (pinfunction "K_K") (pintype "passive"))
    )
    (net (code "95") (name "/TEMP-_1") (class "Default")
      (node (ref "J43") (pin "K") (pinfunction "K_K") (pintype "passive"))
    )
    (net (code "96") (name "/TEMP-_2") (class "Default")
      (node (ref "J44") (pin "K") (pinfunction "K_K") (pintype "passive"))
    )
    (net (code "97") (name "/TEMP-_3") (class "Default")
      (node (ref "J45") (pin "K") (pinfunction "K_K") (pintype "passive"))
    )
    (net (code "98") (name "/TEMP-_4") (class "Default")
      (node (ref "J46") (pin "K") (pinfunction "K_K") (pintype "passive"))
    )
    (net (code "99") (name "/TEMP-_5") (class "Default")
      (node (ref "J47") (pin "K") (pinfunction "K_K") (pintype "passive"))
    )
    (net (code "100") (name "/TEMP-_6") (class "Default")
      (node (ref "J48") (pin "K") (pinfunction "K_K") (pintype "passive"))
    )
    (net (code "101") (name "/TEMP-_7") (class "Default")
      (node (ref "J49") (pin "K") (pinfunction "K_K") (pintype "passive"))
    )
    (net (code "102") (name "/TEMP-_8") (class "Default")
      (node (ref "J50") (pin "K") (pinfunction "K_K") (pintype "passive"))
    )
    (net (code "103") (name "/TEMP-_9") (class "Default")
      (node (ref "J51") (pin "K") (pinfunction "K_K") (pintype "passive"))
    )
    (net (code "104") (name "/TEMP-_10") (class "Default")
      (node (ref "J52") (pin "K") (pinfunction "K_K") (pintype "passive"))
    )
    (net (code "105") (name "/TEMP-_11") (class "Default")
      (node (ref "J53") (pin "K") (pinfunction "K_K") (pintype "passive"))
    )
    (net (code "107") (name "/USB_DM") (class "Default")
      (node (ref "J61") (pin "2") (pinfunction "D-_2") (pintype "passive"))
    )
    (net (code "108") (name "/USB_DP") (class "Default")
      (node (ref "J61") (pin "3") (pinfunction "D+_3") (pintype "passive"))
    )
    (net (code "118") (name "120VAC") (class "Default")
      (node (ref "U1") (pin "2") (pinfunction "2_2") (pintype "passive"))
    )
    (net (code "119") (name "120VAC_RETURN") (class "Default")
      (node (ref "J1") (pin "N") (pinfunction "N_N") (pintype "passive"))
      (node (ref "J10") (pin "1") (pinfunction "1_1") (pintype "passive"))
      (node (ref "J11") (pin "1") (pinfunction "1_1") (pintype "passive"))
      (node (ref "J12") (pin "1") (pinfunction "1_1") (pintype "passive"))
      (node (ref "J13") (pin "1") (pinfunction "1_1") (pintype "passive"))
      (node (ref "J14") (pin "1") (pinfunction "1_1") (pintype "passive"))
      (node (ref "J15") (pin "1") (pinfunction "1_1") (pintype "passive"))
      (node (ref "J16") (pin "1") (pinfunction "1_1") (pintype "passive"))
      (node (ref "J17") (pin "1") (pinfunction "1_1") (pintype "passive"))
      (node (ref "J30") (pin "1") (pinfunction "1_1") (pintype "passive"))
      (node (ref "J31") (pin "1") (pinfunction "1_1") (pintype "passive"))
      (node (ref "J32") (pin "1") (pinfunction "1_1") (pintype "passive"))
      (node (ref "J33") (pin "1") (pinfunction "1_1") (pintype "passive"))
      (node (ref "J34") (pin "1") (pinfunction "1_1") (pintype "passive"))
      (node (ref "J35") (pin "1") (pinfunction "1_1") (pintype "passive"))
      (node (ref "J36") (pin "1") (pinfunction "1_1") (pintype "passive"))
      (node (ref "J37") (pin "1") (pinfunction "1_1") (pintype "passive"))
      (node (ref "J38") (pin "1") (pinfunction "1_1") (pintype "passive"))
      (node (ref "J39") (pin "1") (pinfunction "1_1") (pintype "passive"))
      (node (ref "J40") (pin "1") (pinfunction "1_1") (pintype "passive"))
      (node (ref "J41") (pin "1") (pinfunction "1_1") (pintype "passive"))
    )
    (net (code "120") (name "EARTH_GROUND") (class "Default")
      (node (ref "J1") (pin "E") (pinfunction "G_E") (pintype "passive"))
    )
    (net (code "121") (name "GND") (class "Default")
      (node (ref "J54") (pin "1-2") (pinfunction "1-2_1-2") (pintype "passive"))
      (node (ref "J54") (pin "1-4") (pinfunction "1-4_1-4") (pintype "passive"))
      (node (ref "J54") (pin "1-5") (pinfunction "1-5_1-5") (pintype "passive"))
      (node (ref "J54") (pin "1-7") (pinfunction "1-7_1-7") (pintype "passive"))
      (node (ref "J54") (pin "11-2") (pinfunction "11-2_11-2") (pintype "passive"))
      (node (ref "J54") (pin "11-4") (pinfunction "11-4_11-4") (pintype "passive"))
      (node (ref "J54") (pin "11-6") (pinfunction "11-6_11-6") (pintype "passive"))
      (node (ref "J54") (pin "11-8") (pinfunction "11-8_11-8") (pintype "passive"))
      (node (ref "J54") (pin "12-1") (pinfunction "12-1_12-1") (pintype "passive"))
      (node (ref "J54") (pin "12-3") (pinfunction "12-3_12-3") (pintype "passive"))
      (node (ref "J54") (pin "12-5") (pinfunction "12-5_12-5") (pintype "passive"))
      (node (ref "J54") (pin "12-7") (pinfunction "12-7_12-7") (pintype "passive"))
      (node (ref "J54") (pin "2-2") (pinfunction "2-2_2-2") (pintype "passive"))
      (node (ref "J54") (pin "2-4") (pinfunction "2-4_2-4") (pintype "passive"))
      (node (ref "J54") (pin "2-5") (pinfunction "2-5_2-5") (pintype "passive"))
      (node (ref "J54") (pin "2-7") (pinfunction "2-7_2-7") (pintype "passive"))
      (node (ref "J54") (pin "3-2") (pinfunction "3-2_3-2") (pintype "passive"))
      (node (ref "J54") (pin "3-4") (pinfunction "3-4_3-4") (pintype "passive"))
      (node (ref "J54") (pin "3-5") (pinfunction "3-5_3-5") (pintype "passive"))
      (node (ref "J54") (pin "3-7") (pinfunction "3-7_3-7") (pintype "passive"))
      (node (ref "J54") (pin "4-2") (pinfunction "4-2_4-2") (pintype "passive"))
      (node (ref "J54") (pin "4-4") (pinfunction "4-4_4-4") (pintype "passive"))
      (node (ref "J54") (pin "4-5") (pinfunction "4-5_4-5") (pintype "passive"))
      (node (ref "J54") (pin "4-7") (pinfunction "4-7_4-7") (pintype "passive"))
      (node (ref "J54") (pin "5-2") (pinfunction "5-2_5-2") (pintype "passive"))
      (node (ref "J54") (pin "5-4") (pinfunction "5-4_5-4") (pintype "passive"))
      (node (ref "J54") (pin "5-6") (pinfunction "5-6_5-6") (pintype "passive"))
      (node (ref "J54") (pin "5-8") (pinfunction "5-8_5-8") (pintype "passive"))
      (node (ref "J54") (pin "6-2") (pinfunction "6-2_6-2") (pintype "passive"))
      (node (ref "J54") (pin "6-4") (pinfunction "6-4_6-4") (pintype "passive"))
      (node (ref "J54") (pin "6-6") (pinfunction "6-6_6-6") (pintype "passive"))
      (node (ref "J54") (pin "6-8") (pinfunction "6-8_6-8") (pintype "passive"))
      (node (ref "J54") (pin "7-2") (pinfunction "7-2_7-2") (pintype "passive"))
      (node (ref "J54") (pin "7-4") (pinfunction "7-4_7-4") (pintype "passive"))
      (node (ref "J54") (pin "7-5") (pinfunction "7-5_7-5") (pintype "passive"))
      (node (ref "J54") (pin "7-7") (pinfunction "7-7_7-7") (pintype "passive"))
      (node (ref "J54") (pin "8-2") (pinfunction "8-2_8-2") (pintype "passive"))
      (node (ref "J54") (pin "8-4") (pinfunction "8-4_8-4") (pintype "passive"))
      (node (ref "J54") (pin "8-5") (pinfunction "8-5_8-5") (pintype "passive"))
      (node (ref "J54") (pin "8-7") (pinfunction "8-7_8-7") (pintype "passive"))
      (node (ref "J54") (pin "9-2") (pinfunction "9-2_9-2") (pintype "passive"))
      (node (ref "J54") (pin "9-4") (pinfunction "9-4_9-4") (pintype "passive"))
      (node (ref "J54") (pin "9-5") (pinfunction "9-5_9-5") (pintype "passive"))
      (node (ref "J54") (pin "9-7") (pinfunction "9-7_9-7") (pintype "passive"))
      (node (ref "J61") (pin "5") (pinfunction "GND_5") (pintype "passive"))
      (node (ref "J61") (pin "MH1") (pinfunction "Tab_MH1") (pintype "passive"))
      (node (ref "J61") (pin "MH2") (pinfunction "Tab_MH2") (pintype "passive"))
      (node (ref "J61") (pin "MH3") (pinfunction "Tab_MH3") (pintype "passive"))
      (node (ref "J61") (pin "MH4") (pinfunction "Tab_MH4") (pintype "passive"))
      (node (ref "U43") (pin "22") (pinfunction "22_22") (pintype "passive"))
    )
    (net (code "122") (name "MFC_+15v") (class "Default")
      (node (ref "J54") (pin "1-1") (pinfunction "1-1_1-1") (pintype "passive"))
      (node (ref "J54") (pin "2-1") (pinfunction "2-1_2-1") (pintype "passive"))
      (node (ref "J54") (pin "3-1") (pinfunction "3-1_3-1") (pintype "passive"))
      (node (ref "J54") (pin "4-1") (pinfunction "4-1_4-1") (pintype "passive"))
      (node (ref "J54") (pin "7-1") (pinfunction "7-1_7-1") (pintype "passive"))
      (node (ref "J54") (pin "8-1") (pinfunction "8-1_8-1") (pintype "passive"))
      (node (ref "J54") (pin "9-1") (pinfunction "9-1_9-1") (pintype "passive"))
    )
    (net (code "123") (name "MFC_-15v") (class "Default")
      (node (ref "J54") (pin "1-3") (pinfunction "1-3_1-3") (pintype "passive"))
      (node (ref "J54") (pin "2-3") (pinfunction "2-3_2-3") (pintype "passive"))
      (node (ref "J54") (pin "3-3") (pinfunction "3-3_3-3") (pintype "passive"))
      (node (ref "J54") (pin "4-3") (pinfunction "4-3_4-3") (pintype "passive"))
      (node (ref "J54") (pin "7-3") (pinfunction "7-3_7-3") (pintype "passive"))
      (node (ref "J54") (pin "8-3") (pinfunction "8-3_8-3") (pintype "passive"))
      (node (ref "J54") (pin "9-3") (pinfunction "9-3_9-3") (pintype "passive"))
    )
    (net (code "124") (name "Net-(J1-PadL)") (class "Default")
      (node (ref "J1") (pin "L") (pinfunction "L_L") (pintype "passive"))
      (node (ref "U1") (pin "1") (pinfunction "1_1") (pintype "passive"))
    )
    (net (code "125") (name "Net-(U43-GND)") (class "Default")
      (node (ref "U43") (pin "14") (pinfunction "14_14") (pintype "passive"))
      (node (ref "U43") (pin "3") (pinfunction "GND_3") (pintype "passive"))
    )
    (net (code "126") (name "Net-(U43-Pad15)") (class "Default")
      (node (ref "U43") (pin "15") (pinfunction "15_15") (pintype "passive"))
      (node (ref "U43") (pin "2") (pinfunction "SW_2") (pintype "passive"))
    )
    (net (code "127") (name "Net-(U43-Pad16)") (class "Default")
      (node (ref "U43") (pin "1") (pinfunction "SW_1") (pintype "passive"))
      (node (ref "U43") (pin "16") (pinfunction "16_16") (pintype "passive"))
    )
    (net (code "128") (name "Net-(U43-SCK)") (class "Default")
      (node (ref "U43") (pin "10") (pinfunction "10_10") (pintype "passive"))
      (node (ref "U43") (pin "7") (pinfunction "SCK_7") (pintype "passive"))
    )
    (net (code "129") (name "Net-(U43-SDI)") (class "Default")
      (node (ref "U43") (pin "11") (pinfunction "11_11") (pintype "passive"))
      (node (ref "U43") (pin "6") (pinfunction "SDI_6") (pintype "passive"))
    )
    (net (code "130") (name "Net-(U43-SDO)") (class "Default")
      (node (ref "U43") (pin "12") (pinfunction "12_12") (pintype "passive"))
      (node (ref "U43") (pin "5") (pinfunction "SDO_5") (pintype "passive"))
    )
    (net (code "131") (name "Net-(U43-VDD)") (class "Default")
      (node (ref "U43") (pin "13") (pinfunction "13_13") (pintype "passive"))
      (node (ref "U43") (pin "4") (pinfunction "VDD_4") (pintype "passive"))
    )
    (net (code "132") (name "Net-(U43-~{SS})") (class "Default")
      (node (ref "U43") (pin "8") (pinfunction "~{SS}_8") (pintype "passive"))
      (node (ref "U43") (pin "9") (pinfunction "9_9") (pintype "passive"))
    )
    (net (code "133") (name "VBUS") (class "Default")
      (node (ref "J61") (pin "1") (pinfunction "V_BUS_(5V)_1") (pintype "passive"))
    )
    (net (code "134") (name "unconnected-(J54-Pad10-5)") (class "Default")
      (node (ref "J54") (pin "10-5") (pinfunction "10-5_10-5") (pintype "passive"))
    )
    (net (code "135") (name "unconnected-(J54-Pad10-6)") (class "Default")
      (node (ref "J54") (pin "10-6") (pinfunction "10-6_10-6") (pintype "passive"))
    )
    (net (code "136") (name "unconnected-(J54-Pad10-7)") (class "Default")
      (node (ref "J54") (pin "10-7") (pinfunction "10-7_10-7") (pintype "passive"))
    )
    (net (code "137") (name "unconnected-(J54-Pad10-8)") (class "Default")
      (node (ref "J54") (pin "10-8") (pinfunction "10-8_10-8") (pintype "passive"))
    )
    (net (code "138") (name "unconnected-(J61-NC-Pad4)") (class "Default")
      (node (ref "J61") (pin "4") (pinfunction "NC_4") (pintype "passive"))
    )
    (net (code "139") (name "unconnected-(U43-Pad20)") (class "Default")
      (node (ref "U43") (pin "20") (pinfunction "20_20") (pintype "passive"))
    )
  )
)
